# power.net
KiCad netlist of a schematic drawn in Altium Designer
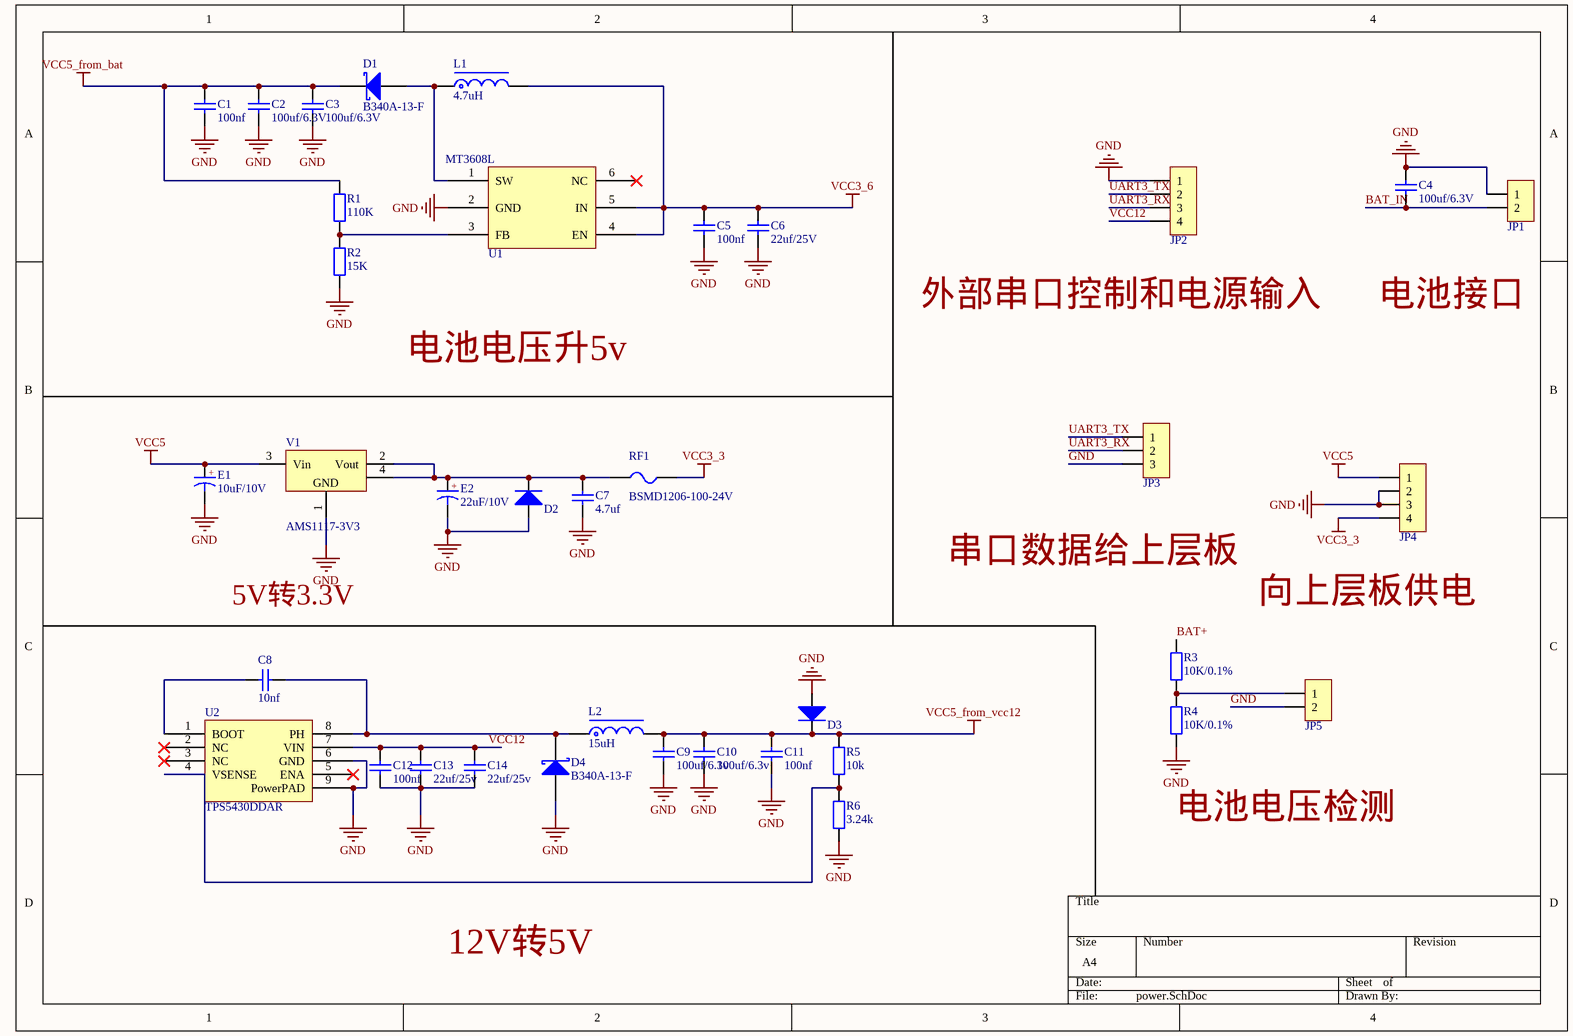
[diagram p0: power.SchDoc]

(export (version "E")
  (design (tool "Eeschema 10.0.6"))
  (components
    (comp (ref "C1")
      (value "100nf")
      (footprint "C0603_L")
      (description "贴片电容/MLCC电容")
      (libsource (lib "0.1 - 电阻-电容-电感-保险丝-晶振-晶体-磁珠-电位器-法拉电容-馈通电容") (part "C"))
    )
    (comp (ref "C2")
      (value "100uf/6.3V")
      (footprint "C1206_L")
      (description "贴片电容/MLCC电容")
      (libsource (lib "0.1 - 电阻-电容-电感-保险丝-晶振-晶体-磁珠-电位器-法拉电容-馈通电容") (part "C"))
    )
    (comp (ref "C3")
      (value "100uf/6.3V")
      (footprint "C1206_L")
      (description "贴片电容/MLCC电容")
      (libsource (lib "0.1 - 电阻-电容-电感-保险丝-晶振-晶体-磁珠-电位器-法拉电容-馈通电容") (part "C"))
    )
    (comp (ref "C4")
      (value "100uf/6.3V")
      (footprint "C1206_L")
      (description "贴片电容/MLCC电容")
      (libsource (lib "0.1 - 电阻-电容-电感-保险丝-晶振-晶体-磁珠-电位器-法拉电容-馈通电容") (part "C"))
    )
    (comp (ref "C5")
      (value "100nf")
      (footprint "C0603_L")
      (description "贴片电容/MLCC电容")
      (libsource (lib "0.1 - 电阻-电容-电感-保险丝-晶振-晶体-磁珠-电位器-法拉电容-馈通电容") (part "C"))
    )
    (comp (ref "C6")
      (value "22uf/25V")
      (footprint "C1206_L")
      (description "贴片电容/MLCC电容")
      (libsource (lib "0.1 - 电阻-电容-电感-保险丝-晶振-晶体-磁珠-电位器-法拉电容-馈通电容") (part "C"))
    )
    (comp (ref "C7")
      (value "4.7uf")
      (footprint "C0603_M")
      (description "贴片电容/MLCC电容")
      (libsource (lib "0.1 - 电阻-电容-电感-保险丝-晶振-晶体-磁珠-电位器-法拉电容-馈通电容") (part "C"))
    )
    (comp (ref "C8")
      (value "10nf")
      (footprint "C0603_L")
      (description "贴片电容/MLCC电容")
      (libsource (lib "0.1 - 电阻-电容-电感-保险丝-晶振-晶体-磁珠-电位器-法拉电容-馈通电容") (part "C"))
    )
    (comp (ref "C9")
      (value "100uf/6.3v")
      (footprint "C1206_L")
      (description "贴片电容/MLCC电容 C15008")
      (libsource (lib "0.1 - 电阻-电容-电感-保险丝-晶振-晶体-磁珠-电位器-法拉电容-馈通电容") (part "C"))
    )
    (comp (ref "C10")
      (value "100uf/6.3v")
      (footprint "C1206_L")
      (description "贴片电容/MLCC电容 C15008")
      (libsource (lib "0.1 - 电阻-电容-电感-保险丝-晶振-晶体-磁珠-电位器-法拉电容-馈通电容") (part "C"))
    )
    (comp (ref "C11")
      (value "100nf")
      (footprint "C0603_L")
      (description "贴片电容/MLCC电容")
      (libsource (lib "0.1 - 电阻-电容-电感-保险丝-晶振-晶体-磁珠-电位器-法拉电容-馈通电容") (part "C"))
    )
    (comp (ref "C12")
      (value "100nf")
      (footprint "C0603_L")
      (description "贴片电容/MLCC电容")
      (libsource (lib "0.1 - 电阻-电容-电感-保险丝-晶振-晶体-磁珠-电位器-法拉电容-馈通电容") (part "C"))
    )
    (comp (ref "C13")
      (value "22uf/25v")
      (footprint "C1206_L")
      (description "贴片电容/MLCC电容")
      (libsource (lib "0.1 - 电阻-电容-电感-保险丝-晶振-晶体-磁珠-电位器-法拉电容-馈通电容") (part "C"))
    )
    (comp (ref "C14")
      (value "22uf/25v")
      (footprint "C1206_L")
      (description "贴片电容/MLCC电容 C12891")
      (libsource (lib "0.1 - 电阻-电容-电感-保险丝-晶振-晶体-磁珠-电位器-法拉电容-馈通电容") (part "C"))
    )
    (comp (ref "D1")
      (value "B340A-13-F")
      (footprint "SMA")
      (description "肖特基二极管 C85098")
      (libsource (lib "HT") (part "B340A-13-F"))
    )
    (comp (ref "D2")
      (value "UDD32C03L01")
      (footprint "SOD-323")
      (description "TVS通用 C78439")
      (libsource (lib "0.2 - 二极管-TVS-ESD-整流桥-放电管") (part "TVS"))
    )
    (comp (ref "D3")
      (value "SMF5.0A")
      (footprint "SOD-123")
      (description "TVS通用")
      (libsource (lib "0.2 - 二极管-TVS-ESD-整流桥-放电管") (part "TVS"))
    )
    (comp (ref "D4")
      (value "B340A-13-F")
      (footprint "SMA")
      (description "肖特基二极管 C85098")
      (libsource (lib "HT") (part "B340A-13-F"))
    )
    (comp (ref "E1")
      (value "10uF/10V")
      (footprint "C_3216")
      (description "贴片钽电容 C7171")
      (libsource (lib "0.1 - 电阻-电容-电感-保险丝-晶振-晶体-磁珠-电位器-法拉电容-馈通电容") (part "CT"))
    )
    (comp (ref "E2")
      (value "22uF/10V")
      (footprint "C_3216")
      (description "贴片钽电容  C11366")
      (libsource (lib "0.1 - 电阻-电容-电感-保险丝-晶振-晶体-磁珠-电位器-法拉电容-馈通电容") (part "CT"))
    )
    (comp (ref "JP1")
      (value "HDR-1X2")
      (footprint "PH2.0-W-2P")
      (description "2P接插件")
      (libsource (lib "5.4 - 2.0mm连接器(PHB2.0_PHD2.0_2.0排针排母)") (part "Header 2"))
    )
    (comp (ref "JP2")
      (value "HDR-1X4")
      (footprint "PH2.0-W-4P")
      (description "4P接插件")
      (libsource (lib "5.4 - 2.0mm连接器(PHB2.0_PHD2.0_2.0排针排母)") (part "Header 4"))
    )
    (comp (ref "JP3")
      (value "HDR-1X3")
      (footprint "HDR2.54-LI-3P")
      (description "3P接插件")
      (libsource (lib "5.5 - 2.54mm连接器(KF2EDGK_XH2.54_2.54排针排母)") (part "Header 3"))
    )
    (comp (ref "JP4")
      (value "HDR-1X4")
      (footprint "HDR2.54-LI-4P")
      (description "4P接插件")
      (libsource (lib "5.5 - 2.54mm连接器(KF2EDGK_XH2.54_2.54排针排母)") (part "Header 4"))
    )
    (comp (ref "JP5")
      (value "HDR-1X2")
      (footprint "HDR2.54-LI-2P")
      (description "2P接插件")
      (libsource (lib "5.5 - 2.54mm连接器(KF2EDGK_XH2.54_2.54排针排母)") (part "Header 2"))
    )
    (comp (ref "L1")
      (value "4.7uH")
      (footprint "CD53")
      (description "CD系列贴片线绕功率电感")
      (libsource (lib "0.1 - 电阻-电容-电感-保险丝-晶振-晶体-磁珠-电位器-法拉电容-馈通电容") (part "L-SMD"))
    )
    (comp (ref "L2")
      (value "15uH")
      (footprint "CD75")
      (description "CD系列贴片线绕功率电感")
      (libsource (lib "0.1 - 电阻-电容-电感-保险丝-晶振-晶体-磁珠-电位器-法拉电容-馈通电容") (part "L-SMD"))
    )
    (comp (ref "R1")
      (value "110K")
      (footprint "R0603_L")
      (description "贴片电阻")
      (libsource (lib "0.1 - 电阻-电容-电感-保险丝-晶振-晶体-磁珠-电位器-法拉电容-馈通电容") (part "R"))
    )
    (comp (ref "R2")
      (value "15K")
      (footprint "R0603_L")
      (description "贴片电阻")
      (libsource (lib "0.1 - 电阻-电容-电感-保险丝-晶振-晶体-磁珠-电位器-法拉电容-馈通电容") (part "R"))
    )
    (comp (ref "R3")
      (value "10K/0.1%")
      (footprint "R0603_L")
      (description "贴片电阻")
      (libsource (lib "0.1 - 电阻-电容-电感-保险丝-晶振-晶体-磁珠-电位器-法拉电容-馈通电容") (part "R"))
    )
    (comp (ref "R4")
      (value "10K/0.1%")
      (footprint "R0603_L")
      (description "贴片电阻")
      (libsource (lib "0.1 - 电阻-电容-电感-保险丝-晶振-晶体-磁珠-电位器-法拉电容-馈通电容") (part "R"))
    )
    (comp (ref "R5")
      (value "10k")
      (footprint "R0603_L")
      (description "贴片电阻")
      (libsource (lib "0.1 - 电阻-电容-电感-保险丝-晶振-晶体-磁珠-电位器-法拉电容-馈通电容") (part "R"))
    )
    (comp (ref "R6")
      (value "3.24k")
      (footprint "R0603_L")
      (description "贴片电阻")
      (libsource (lib "0.1 - 电阻-电容-电感-保险丝-晶振-晶体-磁珠-电位器-法拉电容-馈通电容") (part "R"))
    )
    (comp (ref "RF1")
      (value "BSMD1206-100-24V")
      (footprint "F1206")
      (description "PPTC自恢复保险丝 C910830")
      (libsource (lib "0.1 - 电阻-电容-电感-保险丝-晶振-晶体-磁珠-电位器-法拉电容-馈通电容") (part "FUSE-PPTC"))
    )
    (comp (ref "U1")
      (value "MT3608L")
      (footprint "SOT23-6M")
      (description "Boost升压DC-DC芯片 2-28V")
      (libsource (lib "HT") (part "MT3608L"))
    )
    (comp (ref "U2")
      (value "TPS5430DDAR")
      (footprint "SOIC-8_EP")
      (description "5.5v到36v转1.3v到32v")
      (libsource (lib "HT") (part "TPS5430DDAR"))
    )
    (comp (ref "V1")
      (value "AMS1117-3V3")
      (footprint "SOT223_L")
      (description "三端稳压芯片")
      (libsource (lib "0.7 - 电源类芯片") (part "AMS1117"))
    )
  )
  (nets
    (net (code "1") (name "/BAT+") (class "Default")
      (node (ref "R3") (pin "2") (pinfunction "2_2") (pintype "passive"))
    )
    (net (code "2") (name "/BAT_IN") (class "Default")
      (node (ref "C4") (pin "1") (pinfunction "1_1") (pintype "passive"))
      (node (ref "JP1") (pin "2") (pinfunction "2_2") (pintype "passive"))
    )
    (net (code "3") (name "/UART3_RX") (class "Default")
      (node (ref "JP2") (pin "3") (pinfunction "3_3") (pintype "passive"))
      (node (ref "JP3") (pin "2") (pinfunction "2_2") (pintype "passive"))
    )
    (net (code "4") (name "/UART3_TX") (class "Default")
      (node (ref "JP2") (pin "2") (pinfunction "2_2") (pintype "passive"))
      (node (ref "JP3") (pin "1") (pinfunction "1_1") (pintype "passive"))
    )
    (net (code "5") (name "/VCC12") (class "Default")
      (node (ref "C12") (pin "2") (pinfunction "2_2") (pintype "passive"))
      (node (ref "C13") (pin "2") (pinfunction "2_2") (pintype "passive"))
      (node (ref "C14") (pin "2") (pinfunction "2_2") (pintype "passive"))
      (node (ref "JP2") (pin "4") (pinfunction "4_4") (pintype "passive"))
      (node (ref "U2") (pin "7") (pinfunction "VIN_7") (pintype "passive"))
    )
    (net (code "6") (name "GND") (class "Default")
      (node (ref "C1") (pin "1") (pinfunction "1_1") (pintype "passive"))
      (node (ref "C10") (pin "1") (pinfunction "1_1") (pintype "passive"))
      (node (ref "C11") (pin "1") (pinfunction "1_1") (pintype "passive"))
      (node (ref "C12") (pin "1") (pinfunction "1_1") (pintype "passive"))
      (node (ref "C13") (pin "1") (pinfunction "1_1") (pintype "passive"))
      (node (ref "C14") (pin "1") (pinfunction "1_1") (pintype "passive"))
      (node (ref "C2") (pin "1") (pinfunction "1_1") (pintype "passive"))
      (node (ref "C3") (pin "1") (pinfunction "1_1") (pintype "passive"))
      (node (ref "C4") (pin "2") (pinfunction "2_2") (pintype "passive"))
      (node (ref "C5") (pin "1") (pinfunction "1_1") (pintype "passive"))
      (node (ref "C6") (pin "1") (pinfunction "1_1") (pintype "passive"))
      (node (ref "C7") (pin "2") (pinfunction "2_2") (pintype "passive"))
      (node (ref "C9") (pin "1") (pinfunction "1_1") (pintype "passive"))
      (node (ref "D2") (pin "1") (pinfunction "A_1") (pintype "passive"))
      (node (ref "D3") (pin "1") (pinfunction "A_1") (pintype "passive"))
      (node (ref "D4") (pin "1") (pinfunction "A_1") (pintype "passive"))
      (node (ref "E1") (pin "2") (pinfunction "K_2") (pintype "passive"))
      (node (ref "E2") (pin "2") (pinfunction "K_2") (pintype "passive"))
      (node (ref "JP1") (pin "1") (pinfunction "1_1") (pintype "passive"))
      (node (ref "JP2") (pin "1") (pinfunction "1_1") (pintype "passive"))
      (node (ref "JP3") (pin "3") (pinfunction "3_3") (pintype "passive"))
      (node (ref "JP4") (pin "2") (pinfunction "2_2") (pintype "passive"))
      (node (ref "JP4") (pin "3") (pinfunction "3_3") (pintype "passive"))
      (node (ref "JP5") (pin "2") (pinfunction "2_2") (pintype "passive"))
      (node (ref "R2") (pin "1") (pinfunction "1_1") (pintype "passive"))
      (node (ref "R4") (pin "1") (pinfunction "1_1") (pintype "passive"))
      (node (ref "R6") (pin "1") (pinfunction "1_1") (pintype "passive"))
      (node (ref "U1") (pin "2") (pinfunction "GND_2") (pintype "passive"))
      (node (ref "U2") (pin "6") (pinfunction "GND_6") (pintype "passive"))
      (node (ref "U2") (pin "9") (pinfunction "PowerPAD_9") (pintype "passive"))
      (node (ref "V1") (pin "1") (pinfunction "GND_1") (pintype "passive"))
    )
    (net (code "7") (name "Net-(D1-A)") (class "Default")
      (node (ref "D1") (pin "1") (pinfunction "A_1") (pintype "passive"))
      (node (ref "L1") (pin "1") (pinfunction "1_1") (pintype "passive"))
      (node (ref "U1") (pin "1") (pinfunction "SW_1") (pintype "passive"))
    )
    (net (code "8") (name "Net-(D2-K)") (class "Default")
      (node (ref "C7") (pin "1") (pinfunction "1_1") (pintype "passive"))
      (node (ref "D2") (pin "2") (pinfunction "K_2") (pintype "passive"))
      (node (ref "E2") (pin "1") (pinfunction "A_1") (pintype "passive"))
      (node (ref "RF1") (pin "2") (pinfunction "2_2") (pintype "passive"))
      (node (ref "V1") (pin "2") (pinfunction "Vout_2") (pintype "passive"))
      (node (ref "V1") (pin "4") (pinfunction "GND_4") (pintype "passive"))
    )
    (net (code "9") (name "Net-(D4-K)") (class "Default")
      (node (ref "C8") (pin "2") (pinfunction "2_2") (pintype "passive"))
      (node (ref "D4") (pin "2") (pinfunction "K_2") (pintype "passive"))
      (node (ref "L2") (pin "1") (pinfunction "1_1") (pintype "passive"))
      (node (ref "U2") (pin "8") (pinfunction "PH_8") (pintype "passive"))
    )
    (net (code "10") (name "Net-(JP5-Pad1)") (class "Default")
      (node (ref "JP5") (pin "1") (pinfunction "1_1") (pintype "passive"))
      (node (ref "R3") (pin "1") (pinfunction "1_1") (pintype "passive"))
      (node (ref "R4") (pin "2") (pinfunction "2_2") (pintype "passive"))
    )
    (net (code "11") (name "Net-(U1-FB)") (class "Default")
      (node (ref "R1") (pin "1") (pinfunction "1_1") (pintype "passive"))
      (node (ref "R2") (pin "2") (pinfunction "2_2") (pintype "passive"))
      (node (ref "U1") (pin "3") (pinfunction "FB_3") (pintype "passive"))
    )
    (net (code "12") (name "Net-(U2-BOOT)") (class "Default")
      (node (ref "C8") (pin "1") (pinfunction "1_1") (pintype "passive"))
      (node (ref "U2") (pin "1") (pinfunction "BOOT_1") (pintype "passive"))
    )
    (net (code "13") (name "Net-(U2-VSENSE)") (class "Default")
      (node (ref "R5") (pin "1") (pinfunction "1_1") (pintype "passive"))
      (node (ref "R6") (pin "2") (pinfunction "2_2") (pintype "passive"))
      (node (ref "U2") (pin "4") (pinfunction "VSENSE_4") (pintype "passive"))
    )
    (net (code "14") (name "VCC3_3") (class "Default")
      (node (ref "JP4") (pin "4") (pinfunction "4_4") (pintype "passive"))
      (node (ref "RF1") (pin "1") (pinfunction "1_1") (pintype "passive"))
    )
    (net (code "15") (name "VCC3_6") (class "Default")
      (node (ref "C5") (pin "2") (pinfunction "2_2") (pintype "passive"))
      (node (ref "C6") (pin "2") (pinfunction "2_2") (pintype "passive"))
      (node (ref "L1") (pin "2") (pinfunction "2_2") (pintype "passive"))
      (node (ref "U1") (pin "4") (pinfunction "EN_4") (pintype "passive"))
      (node (ref "U1") (pin "5") (pinfunction "IN_5") (pintype "passive"))
    )
    (net (code "16") (name "VCC5") (class "Default")
      (node (ref "E1") (pin "1") (pinfunction "A_1") (pintype "passive"))
      (node (ref "JP4") (pin "1") (pinfunction "1_1") (pintype "passive"))
      (node (ref "V1") (pin "3") (pinfunction "Vin_3") (pintype "passive"))
    )
    (net (code "17") (name "VCC5_from_bat") (class "Default")
      (node (ref "C1") (pin "2") (pinfunction "2_2") (pintype "passive"))
      (node (ref "C2") (pin "2") (pinfunction "2_2") (pintype "passive"))
      (node (ref "C3") (pin "2") (pinfunction "2_2") (pintype "passive"))
      (node (ref "D1") (pin "2") (pinfunction "K_2") (pintype "passive"))
      (node (ref "R1") (pin "2") (pinfunction "2_2") (pintype "passive"))
    )
    (net (code "18") (name "VCC5_from_vcc12") (class "Default")
      (node (ref "C10") (pin "2") (pinfunction "2_2") (pintype "passive"))
      (node (ref "C11") (pin "2") (pinfunction "2_2") (pintype "passive"))
      (node (ref "C9") (pin "2") (pinfunction "2_2") (pintype "passive"))
      (node (ref "D3") (pin "2") (pinfunction "K_2") (pintype "passive"))
      (node (ref "L2") (pin "2") (pinfunction "2_2") (pintype "passive"))
      (node (ref "R5") (pin "2") (pinfunction "2_2") (pintype "passive"))
    )
    (net (code "19") (name "unconnected-(U1-NC-Pad6)") (class "Default")
      (node (ref "U1") (pin "6") (pinfunction "NC_6") (pintype "passive+no_connect"))
    )
    (net (code "20") (name "unconnected-(U2-ENA-Pad5)") (class "Default")
      (node (ref "U2") (pin "5") (pinfunction "ENA_5") (pintype "passive+no_connect"))
    )
    (net (code "21") (name "unconnected-(U2-NC-Pad2)") (class "Default")
      (node (ref "U2") (pin "2") (pinfunction "NC_2") (pintype "passive+no_connect"))
    )
    (net (code "22") (name "unconnected-(U2-NC-Pad3)") (class "Default")
      (node (ref "U2") (pin "3") (pinfunction "NC_3") (pintype "passive+no_connect"))
    )
  )
)
